# TLM_002_LoRa.net
KiCad netlist of a schematic drawn in Altium Designer
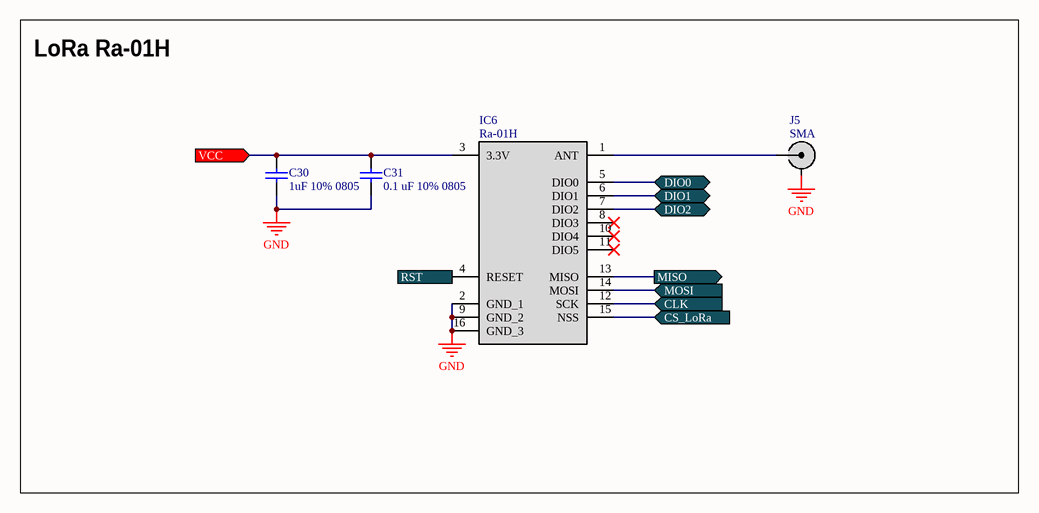
[diagram p0: TLM_002_LoRa.SchDoc]

(export (version "E")
  (design (tool "Eeschema 10.0.6"))
  (components
    (comp (ref "C30")
      (value "1uF 10% 0805")
      (footprint "CAPC2013X145X50NL20T20")
      (fields (field (name "PART NUMBER") "VJ0805Y105KXQRW1BC") (field (name "MANUFACTURER") "Vitramon"))
      (libsource (lib "Altium Content Vault") (part "CAP"))
    )
    (comp (ref "C31")
      (value "0.1 uF 10% 0805")
      (footprint "CAPC2013X140X50ML20T25")
      (fields
        (field (name "PART NUMBER") "0805DD104KAT2A")
        (field (name "MANUFACTURER") "AVX Interconnect / Elco")
      )
      (libsource (lib "Altium Content Vault") (part "CAP"))
    )
    (comp (ref "IC6")
      (value "Ra-01H")
      (footprint "Ra01H")
      (description "Integrated Circuit")
      (libsource (lib "SamacSys") (part "Ra-01H"))
    )
    (comp (ref "J5")
      (value "SMA")
      (footprint "FP-5-1814400-2-MFG")
      (description "RF SMA Connector, 1 Contact(s), Female, Board Mount, Solder Terminal, Locking, Jack")
      (libsource (lib "NAZAR LYSENKO") (part "42d0677c2d2b90080c021db52569f63"))
    )
  )
  (nets
    (net (code "1") (name "/CLK") (class "Default")
      (node (ref "IC6") (pin "12") (pinfunction "SCK_12") (pintype "passive"))
    )
    (net (code "2") (name "/CS_LoRa") (class "Default")
      (node (ref "IC6") (pin "15") (pinfunction "NSS_15") (pintype "passive"))
    )
    (net (code "3") (name "/DIO0") (class "Default")
      (node (ref "IC6") (pin "5") (pinfunction "DIO0_5") (pintype "passive"))
    )
    (net (code "4") (name "/DIO1") (class "Default")
      (node (ref "IC6") (pin "6") (pinfunction "DIO1_6") (pintype "passive"))
    )
    (net (code "5") (name "/DIO2") (class "Default")
      (node (ref "IC6") (pin "7") (pinfunction "DIO2_7") (pintype "passive"))
    )
    (net (code "6") (name "/MISO") (class "Default")
      (node (ref "IC6") (pin "13") (pinfunction "MISO_13") (pintype "passive"))
    )
    (net (code "7") (name "/MOSI") (class "Default")
      (node (ref "IC6") (pin "14") (pinfunction "MOSI_14") (pintype "passive"))
    )
    (net (code "8") (name "/RST") (class "Default")
      (node (ref "IC6") (pin "4") (pinfunction "RESET_4") (pintype "passive"))
    )
    (net (code "9") (name "/VCC") (class "Default")
      (node (ref "C30") (pin "2") (pinfunction "2_2") (pintype "passive"))
      (node (ref "C31") (pin "2") (pinfunction "2_2") (pintype "passive"))
      (node (ref "IC6") (pin "3") (pinfunction "3.3V_3") (pintype "passive"))
    )
    (net (code "10") (name "GND") (class "Default")
      (node (ref "C30") (pin "1") (pinfunction "1_1") (pintype "passive"))
      (node (ref "C31") (pin "1") (pinfunction "1_1") (pintype "passive"))
      (node (ref "IC6") (pin "16") (pinfunction "GND_3_16") (pintype "passive"))
      (node (ref "IC6") (pin "2") (pinfunction "GND_1_2") (pintype "passive"))
      (node (ref "IC6") (pin "9") (pinfunction "GND_2_9") (pintype "passive"))
      (node (ref "J5") (pin "2") (pinfunction "2_2") (pintype "passive"))
    )
    (net (code "11") (name "Net-(IC6-ANT)") (class "Default")
      (node (ref "IC6") (pin "1") (pinfunction "ANT_1") (pintype "passive"))
      (node (ref "J5") (pin "1") (pinfunction "1_1") (pintype "passive"))
    )
    (net (code "12") (name "unconnected-(IC6-DIO3-Pad8)") (class "Default")
      (node (ref "IC6") (pin "8") (pinfunction "DIO3_8") (pintype "passive+no_connect"))
    )
    (net (code "13") (name "unconnected-(IC6-DIO4-Pad10)") (class "Default")
      (node (ref "IC6") (pin "10") (pinfunction "DIO4_10") (pintype "passive+no_connect"))
    )
    (net (code "14") (name "unconnected-(IC6-DIO5-Pad11)") (class "Default")
      (node (ref "IC6") (pin "11") (pinfunction "DIO5_11") (pintype "passive+no_connect"))
    )
  )
)
